# esc.net
KiCad netlist of a schematic drawn in EAGLE
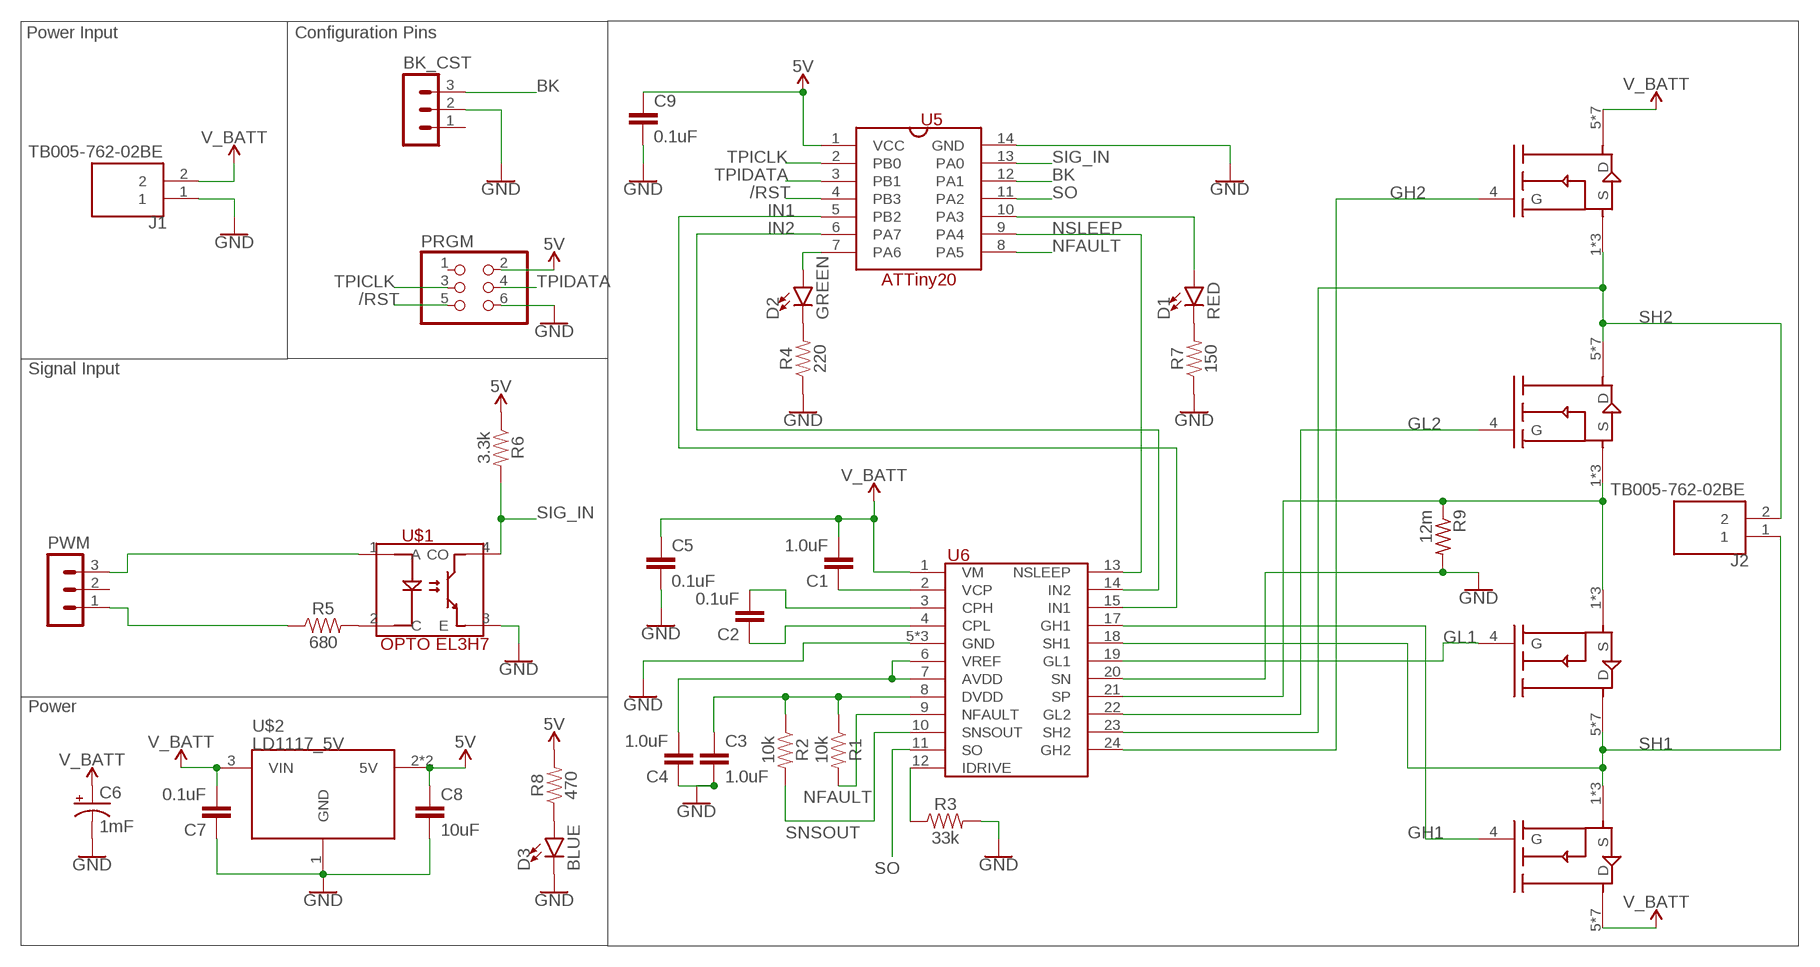
[diagram p0: schematic, sheet 1]

(export (version "E")
  (design (tool "Eeschema 10.0.6"))
  (components
    (comp (ref "BK_CST")
      (value "MA03-1")
      (footprint "eagle-import:MA03-1")
      (libsource (lib "eagle-import") (part "MA03-1"))
    )
    (comp (ref "C1")
      (value "1.0uF")
      (footprint "eagle-import:0603")
      (libsource (lib "eagle-import") (part "1.0UF-0603-16V-10%"))
    )
    (comp (ref "C2")
      (value "0.1uF")
      (footprint "eagle-import:0603")
      (libsource (lib "eagle-import") (part "0.1UF-0603-25V-5%"))
    )
    (comp (ref "C3")
      (value "1.0uF")
      (footprint "eagle-import:0603")
      (libsource (lib "eagle-import") (part "1.0UF-0603-16V-10%"))
    )
    (comp (ref "C4")
      (value "1.0uF")
      (footprint "eagle-import:0603")
      (libsource (lib "eagle-import") (part "1.0UF-0603-16V-10%"))
    )
    (comp (ref "C5")
      (value "0.1uF")
      (footprint "eagle-import:0603")
      (libsource (lib "eagle-import") (part "0.1UF-0603-25V-5%"))
    )
    (comp (ref "C6")
      (value "1mF")
      (footprint "eagle-import:CPOL-RADIAL-5MM-10MM")
      (libsource (lib "eagle-import") (part "1000UF-RADIAL-5MM-25V-20%"))
    )
    (comp (ref "C7")
      (value "0.1uF")
      (footprint "eagle-import:0603")
      (libsource (lib "eagle-import") (part "0.1UF-0603-25V-5%"))
    )
    (comp (ref "C8")
      (value "10uF")
      (footprint "eagle-import:0603")
      (libsource (lib "eagle-import") (part "10UF-0603-6.3V-20%"))
    )
    (comp (ref "C9")
      (value "0.1uF")
      (footprint "eagle-import:0603")
      (libsource (lib "eagle-import") (part "0.1UF-0603-25V-5%"))
    )
    (comp (ref "D1")
      (value "RED")
      (footprint "eagle-import:LED-0603")
      (libsource (lib "eagle-import") (part "LED-RED0603"))
    )
    (comp (ref "D2")
      (value "GREEN")
      (footprint "eagle-import:LED-0603")
      (libsource (lib "eagle-import") (part "LED-GREEN0603"))
    )
    (comp (ref "D3")
      (value "BLUE")
      (footprint "eagle-import:LED-0603")
      (libsource (lib "eagle-import") (part "LED-BLUE0603"))
    )
    (comp (ref "J1")
      (value "TB005-762-02BE")
      (footprint "eagle-import:CUI_TB005-762-02BE")
      (fields (field (name "MANUFACTURER") "CUI"))
      (libsource (lib "eagle-import") (part "TB005-762-02BE"))
    )
    (comp (ref "J2")
      (value "TB005-762-02BE")
      (footprint "eagle-import:CUI_TB005-762-02BE")
      (fields (field (name "MANUFACTURER") "CUI"))
      (libsource (lib "eagle-import") (part "TB005-762-02BE"))
    )
    (comp (ref "PRGM")
      (value "PINHD-2X3")
      (footprint "eagle-import:2X03")
      (libsource (lib "eagle-import") (part "PINHD-2X3"))
    )
    (comp (ref "PWM")
      (value "MA03-1")
      (footprint "eagle-import:MA03-1")
      (libsource (lib "eagle-import") (part "MA03-1"))
    )
    (comp (ref "R1")
      (value "10k")
      (footprint "eagle-import:0603")
      (libsource (lib "eagle-import") (part "10KOHM-0603-1/10W-1%"))
    )
    (comp (ref "R2")
      (value "10k")
      (footprint "eagle-import:0603")
      (libsource (lib "eagle-import") (part "10KOHM-0603-1/10W-1%"))
    )
    (comp (ref "R3")
      (value "33k")
      (footprint "eagle-import:0603")
      (libsource (lib "eagle-import") (part "33KOHM-0603-1/10W-1%"))
    )
    (comp (ref "R4")
      (value "220")
      (footprint "eagle-import:0603")
      (libsource (lib "eagle-import") (part "220OHM-0603-1/10W-1%"))
    )
    (comp (ref "R5")
      (value "680")
      (footprint "eagle-import:0603")
      (libsource (lib "eagle-import") (part "680OHM-0603-1/10W-5%"))
    )
    (comp (ref "R6")
      (value "3.3k")
      (footprint "eagle-import:0603")
      (libsource (lib "eagle-import") (part "3.3KOHM-0603-1/10W-1%"))
    )
    (comp (ref "R7")
      (value "150")
      (footprint "eagle-import:0603")
      (libsource (lib "eagle-import") (part "150OHM-0603-1/10W-1%"))
    )
    (comp (ref "R8")
      (value "470")
      (footprint "eagle-import:0603")
      (libsource (lib "eagle-import") (part "470OHM-0603-1/10W-1%"))
    )
    (comp (ref "R9")
      (value "12m")
      (footprint "eagle-import:R2512")
      (libsource (lib "eagle-import") (part "R-US_R2512"))
    )
    (comp (ref "U$1")
      (value "EL3H7")
      (footprint "eagle-import:SOIC127P700X265-4")
      (libsource (lib "eagle-import") (part "EL3H7"))
    )
    (comp (ref "U$2")
      (value "LD1117_5V")
      (footprint "eagle-import:SOT223")
      (libsource (lib "eagle-import") (part "LD1117_5V"))
    )
    (comp (ref "U1")
      (value "AON6558")
      (footprint "eagle-import:POWER-SO8")
      (libsource (lib "eagle-import") (part "AON6558"))
    )
    (comp (ref "U2")
      (value "AON6558")
      (footprint "eagle-import:POWER-SO8")
      (libsource (lib "eagle-import") (part "AON6558"))
    )
    (comp (ref "U3")
      (value "AON6558")
      (footprint "eagle-import:POWER-SO8")
      (libsource (lib "eagle-import") (part "AON6558"))
    )
    (comp (ref "U4")
      (value "AON6558")
      (footprint "eagle-import:POWER-SO8")
      (libsource (lib "eagle-import") (part "AON6558"))
    )
    (comp (ref "U5")
      (value "ATTINY20")
      (footprint "eagle-import:SOIC127P599X265-14")
      (libsource (lib "eagle-import") (part "ATTINY20"))
    )
    (comp (ref "U6")
      (value "DRV8701")
      (footprint "eagle-import:QFN50P400X400X100-25T280")
      (libsource (lib "eagle-import") (part "DRV8701"))
    )
  )
  (nets
    (net (code "1") (name "/BK") (class "Default")
      (node (ref "BK_CST") (pin "3") (pinfunction "3_3") (pintype "passive"))
      (node (ref "U5") (pin "12") (pinfunction "PA1_12") (pintype "bidirectional"))
    )
    (net (code "2") (name "/GH1") (class "Default")
      (node (ref "U4") (pin "4") (pinfunction "G_4") (pintype "bidirectional"))
      (node (ref "U6") (pin "17") (pinfunction "GH1_17") (pintype "bidirectional"))
    )
    (net (code "3") (name "/GH2") (class "Default")
      (node (ref "U1") (pin "4") (pinfunction "G_4") (pintype "bidirectional"))
      (node (ref "U6") (pin "24") (pinfunction "GH2_24") (pintype "bidirectional"))
    )
    (net (code "4") (name "/GL1") (class "Default")
      (node (ref "U3") (pin "4") (pinfunction "G_4") (pintype "bidirectional"))
      (node (ref "U6") (pin "19") (pinfunction "GL1_19") (pintype "bidirectional"))
    )
    (net (code "5") (name "/GL2") (class "Default")
      (node (ref "U2") (pin "4") (pinfunction "G_4") (pintype "bidirectional"))
      (node (ref "U6") (pin "22") (pinfunction "GL2_22") (pintype "bidirectional"))
    )
    (net (code "6") (name "/IN1") (class "Default")
      (node (ref "U5") (pin "5") (pinfunction "PB2_5") (pintype "bidirectional"))
      (node (ref "U6") (pin "15") (pinfunction "IN1_15") (pintype "bidirectional"))
    )
    (net (code "7") (name "/IN2") (class "Default")
      (node (ref "U5") (pin "6") (pinfunction "PA7_6") (pintype "bidirectional"))
      (node (ref "U6") (pin "14") (pinfunction "IN2_14") (pintype "bidirectional"))
    )
    (net (code "8") (name "/NFAULT") (class "Default")
      (node (ref "R1") (pin "2") (pinfunction "2_2") (pintype "passive"))
      (node (ref "U5") (pin "8") (pinfunction "PA5_8") (pintype "bidirectional"))
      (node (ref "U6") (pin "9") (pinfunction "NFAULT_9") (pintype "bidirectional"))
    )
    (net (code "9") (name "/NSLEEP") (class "Default")
      (node (ref "U5") (pin "9") (pinfunction "PA4_9") (pintype "bidirectional"))
      (node (ref "U6") (pin "13") (pinfunction "NSLEEP_13") (pintype "bidirectional"))
    )
    (net (code "10") (name "/SH1") (class "Default")
      (node (ref "J2") (pin "1") (pinfunction "1_1") (pintype "passive"))
      (node (ref "U3") (pin "5") (pinfunction "D_5") (pintype "bidirectional"))
      (node (ref "U3") (pin "6") (pinfunction "D_6") (pintype "bidirectional"))
      (node (ref "U3") (pin "7") (pinfunction "D_7") (pintype "bidirectional"))
      (node (ref "U3") (pin "8") (pinfunction "D_8") (pintype "bidirectional"))
      (node (ref "U3") (pin "PAD") (pinfunction "D_PAD") (pintype "bidirectional"))
      (node (ref "U3") (pin "SIDEPAD1") (pinfunction "D_SIDEPAD1") (pintype "bidirectional"))
      (node (ref "U3") (pin "SIDEPAD2") (pinfunction "D_SIDEPAD2") (pintype "bidirectional"))
      (node (ref "U4") (pin "1") (pinfunction "S_1") (pintype "bidirectional"))
      (node (ref "U4") (pin "2") (pinfunction "S_2") (pintype "bidirectional"))
      (node (ref "U4") (pin "3") (pinfunction "S_3") (pintype "bidirectional"))
      (node (ref "U6") (pin "18") (pinfunction "SH1_18") (pintype "bidirectional"))
    )
    (net (code "11") (name "/SH2") (class "Default")
      (node (ref "J2") (pin "2") (pinfunction "2_2") (pintype "passive"))
      (node (ref "U1") (pin "1") (pinfunction "S_1") (pintype "bidirectional"))
      (node (ref "U1") (pin "2") (pinfunction "S_2") (pintype "bidirectional"))
      (node (ref "U1") (pin "3") (pinfunction "S_3") (pintype "bidirectional"))
      (node (ref "U2") (pin "5") (pinfunction "D_5") (pintype "bidirectional"))
      (node (ref "U2") (pin "6") (pinfunction "D_6") (pintype "bidirectional"))
      (node (ref "U2") (pin "7") (pinfunction "D_7") (pintype "bidirectional"))
      (node (ref "U2") (pin "8") (pinfunction "D_8") (pintype "bidirectional"))
      (node (ref "U2") (pin "PAD") (pinfunction "D_PAD") (pintype "bidirectional"))
      (node (ref "U2") (pin "SIDEPAD1") (pinfunction "D_SIDEPAD1") (pintype "bidirectional"))
      (node (ref "U2") (pin "SIDEPAD2") (pinfunction "D_SIDEPAD2") (pintype "bidirectional"))
      (node (ref "U6") (pin "23") (pinfunction "SH2_23") (pintype "bidirectional"))
    )
    (net (code "12") (name "/SIG_IN") (class "Default")
      (node (ref "R6") (pin "2") (pinfunction "2_2") (pintype "passive"))
      (node (ref "U$1") (pin "4") (pinfunction "CO_4") (pintype "bidirectional"))
      (node (ref "U5") (pin "13") (pinfunction "PA0_13") (pintype "bidirectional"))
    )
    (net (code "13") (name "/SNSOUT") (class "Default")
      (node (ref "R2") (pin "2") (pinfunction "2_2") (pintype "passive"))
      (node (ref "U6") (pin "10") (pinfunction "SNSOUT_10") (pintype "bidirectional"))
    )
    (net (code "14") (name "/SO") (class "Default")
      (node (ref "U5") (pin "11") (pinfunction "PA2_11") (pintype "bidirectional"))
      (node (ref "U6") (pin "11") (pinfunction "SO_11") (pintype "bidirectional"))
    )
    (net (code "15") (name "/TPICLK") (class "Default")
      (node (ref "PRGM") (pin "3") (pinfunction "3_3") (pintype "passive"))
      (node (ref "U5") (pin "2") (pinfunction "PB0_2") (pintype "bidirectional"))
    )
    (net (code "16") (name "/TPIDATA") (class "Default")
      (node (ref "PRGM") (pin "4") (pinfunction "4_4") (pintype "passive"))
      (node (ref "U5") (pin "3") (pinfunction "PB1_3") (pintype "bidirectional"))
    )
    (net (code "17") (name "/{slash}RST") (class "Default")
      (node (ref "PRGM") (pin "5") (pinfunction "5_5") (pintype "passive"))
      (node (ref "U5") (pin "4") (pinfunction "PB3_4") (pintype "bidirectional"))
    )
    (net (code "18") (name "5V") (class "Default")
      (node (ref "C8") (pin "1") (pinfunction "1_1") (pintype "passive"))
      (node (ref "C9") (pin "1") (pinfunction "1_1") (pintype "passive"))
      (node (ref "PRGM") (pin "2") (pinfunction "2_2") (pintype "passive"))
      (node (ref "R6") (pin "1") (pinfunction "1_1") (pintype "passive"))
      (node (ref "R8") (pin "2") (pinfunction "2_2") (pintype "passive"))
      (node (ref "U$2") (pin "2") (pinfunction "5V_2") (pintype "bidirectional"))
      (node (ref "U$2") (pin "4") (pinfunction "5V_4") (pintype "bidirectional"))
      (node (ref "U5") (pin "1") (pinfunction "VCC_1") (pintype "bidirectional"))
    )
    (net (code "19") (name "GND") (class "Default")
      (node (ref "BK_CST") (pin "2") (pinfunction "2_2") (pintype "passive"))
      (node (ref "C3") (pin "2") (pinfunction "2_2") (pintype "passive"))
      (node (ref "C4") (pin "1") (pinfunction "1_1") (pintype "passive"))
      (node (ref "C5") (pin "2") (pinfunction "2_2") (pintype "passive"))
      (node (ref "C6") (pin "-") (pinfunction "-_-") (pintype "passive"))
      (node (ref "C7") (pin "1") (pinfunction "1_1") (pintype "passive"))
      (node (ref "C8") (pin "2") (pinfunction "2_2") (pintype "passive"))
      (node (ref "C9") (pin "2") (pinfunction "2_2") (pintype "passive"))
      (node (ref "D3") (pin "C") (pinfunction "C_C") (pintype "passive"))
      (node (ref "J1") (pin "1") (pinfunction "1_1") (pintype "passive"))
      (node (ref "PRGM") (pin "6") (pinfunction "6_6") (pintype "passive"))
      (node (ref "R3") (pin "2") (pinfunction "2_2") (pintype "passive"))
      (node (ref "R4") (pin "1") (pinfunction "1_1") (pintype "passive"))
      (node (ref "R7") (pin "1") (pinfunction "1_1") (pintype "passive"))
      (node (ref "R9") (pin "2") (pinfunction "2_2") (pintype "passive"))
      (node (ref "U$1") (pin "3") (pinfunction "E_3") (pintype "bidirectional"))
      (node (ref "U$2") (pin "1") (pinfunction "GND_1") (pintype "bidirectional"))
      (node (ref "U5") (pin "14") (pinfunction "GND_14") (pintype "bidirectional"))
      (node (ref "U6") (pin "16") (pinfunction "GND_16") (pintype "bidirectional"))
      (node (ref "U6") (pin "20") (pinfunction "SN_20") (pintype "bidirectional"))
      (node (ref "U6") (pin "25") (pinfunction "GND_25") (pintype "bidirectional"))
      (node (ref "U6") (pin "5") (pinfunction "GND_5") (pintype "bidirectional"))
    )
    (net (code "20") (name "Net-(D1-PadC)") (class "Default")
      (node (ref "D1") (pin "C") (pinfunction "C_C") (pintype "passive"))
      (node (ref "R7") (pin "2") (pinfunction "2_2") (pintype "passive"))
    )
    (net (code "21") (name "Net-(D2-PadC)") (class "Default")
      (node (ref "D2") (pin "C") (pinfunction "C_C") (pintype "passive"))
      (node (ref "R4") (pin "2") (pinfunction "2_2") (pintype "passive"))
    )
    (net (code "22") (name "Net-(D3-PadA)") (class "Default")
      (node (ref "D3") (pin "A") (pinfunction "A_A") (pintype "passive"))
      (node (ref "R8") (pin "1") (pinfunction "1_1") (pintype "passive"))
    )
    (net (code "23") (name "Net-(PWM-Pad1)") (class "Default")
      (node (ref "PWM") (pin "1") (pinfunction "1_1") (pintype "passive"))
      (node (ref "R5") (pin "1") (pinfunction "1_1") (pintype "passive"))
    )
    (net (code "24") (name "Net-(U$1-A)") (class "Default")
      (node (ref "PWM") (pin "3") (pinfunction "3_3") (pintype "passive"))
      (node (ref "U$1") (pin "1") (pinfunction "A_1") (pintype "bidirectional"))
    )
    (net (code "25") (name "Net-(U$1-C)") (class "Default")
      (node (ref "R5") (pin "2") (pinfunction "2_2") (pintype "passive"))
      (node (ref "U$1") (pin "2") (pinfunction "C_2") (pintype "bidirectional"))
    )
    (net (code "26") (name "Net-(U5-PA3)") (class "Default")
      (node (ref "D1") (pin "A") (pinfunction "A_A") (pintype "passive"))
      (node (ref "U5") (pin "10") (pinfunction "PA3_10") (pintype "bidirectional"))
    )
    (net (code "27") (name "Net-(U5-PA6)") (class "Default")
      (node (ref "D2") (pin "A") (pinfunction "A_A") (pintype "passive"))
      (node (ref "U5") (pin "7") (pinfunction "PA6_7") (pintype "bidirectional"))
    )
    (net (code "28") (name "Net-(U6-AVDD)") (class "Default")
      (node (ref "C4") (pin "2") (pinfunction "2_2") (pintype "passive"))
      (node (ref "U6") (pin "6") (pinfunction "VREF_6") (pintype "bidirectional"))
      (node (ref "U6") (pin "7") (pinfunction "AVDD_7") (pintype "bidirectional"))
    )
    (net (code "29") (name "Net-(U6-CPH)") (class "Default")
      (node (ref "C2") (pin "2") (pinfunction "2_2") (pintype "passive"))
      (node (ref "U6") (pin "3") (pinfunction "CPH_3") (pintype "bidirectional"))
    )
    (net (code "30") (name "Net-(U6-CPL)") (class "Default")
      (node (ref "C2") (pin "1") (pinfunction "1_1") (pintype "passive"))
      (node (ref "U6") (pin "4") (pinfunction "CPL_4") (pintype "bidirectional"))
    )
    (net (code "31") (name "Net-(U6-DVDD)") (class "Default")
      (node (ref "C3") (pin "1") (pinfunction "1_1") (pintype "passive"))
      (node (ref "R1") (pin "1") (pinfunction "1_1") (pintype "passive"))
      (node (ref "R2") (pin "1") (pinfunction "1_1") (pintype "passive"))
      (node (ref "U6") (pin "8") (pinfunction "DVDD_8") (pintype "bidirectional"))
    )
    (net (code "32") (name "Net-(U6-IDRIVE)") (class "Default")
      (node (ref "R3") (pin "1") (pinfunction "1_1") (pintype "passive"))
      (node (ref "U6") (pin "12") (pinfunction "IDRIVE_12") (pintype "bidirectional"))
    )
    (net (code "33") (name "Net-(U6-SP)") (class "Default")
      (node (ref "R9") (pin "1") (pinfunction "1_1") (pintype "passive"))
      (node (ref "U2") (pin "1") (pinfunction "S_1") (pintype "bidirectional"))
      (node (ref "U2") (pin "2") (pinfunction "S_2") (pintype "bidirectional"))
      (node (ref "U2") (pin "3") (pinfunction "S_3") (pintype "bidirectional"))
      (node (ref "U3") (pin "1") (pinfunction "S_1") (pintype "bidirectional"))
      (node (ref "U3") (pin "2") (pinfunction "S_2") (pintype "bidirectional"))
      (node (ref "U3") (pin "3") (pinfunction "S_3") (pintype "bidirectional"))
      (node (ref "U6") (pin "21") (pinfunction "SP_21") (pintype "bidirectional"))
    )
    (net (code "34") (name "Net-(U6-VCP)") (class "Default")
      (node (ref "C1") (pin "1") (pinfunction "1_1") (pintype "passive"))
      (node (ref "U6") (pin "2") (pinfunction "VCP_2") (pintype "bidirectional"))
    )
    (net (code "35") (name "V_BATT") (class "Default")
      (node (ref "C1") (pin "2") (pinfunction "2_2") (pintype "passive"))
      (node (ref "C5") (pin "1") (pinfunction "1_1") (pintype "passive"))
      (node (ref "C6") (pin "+") (pinfunction "+_+") (pintype "passive"))
      (node (ref "C7") (pin "2") (pinfunction "2_2") (pintype "passive"))
      (node (ref "J1") (pin "2") (pinfunction "2_2") (pintype "passive"))
      (node (ref "U$2") (pin "3") (pinfunction "VIN_3") (pintype "bidirectional"))
      (node (ref "U1") (pin "5") (pinfunction "D_5") (pintype "bidirectional"))
      (node (ref "U1") (pin "6") (pinfunction "D_6") (pintype "bidirectional"))
      (node (ref "U1") (pin "7") (pinfunction "D_7") (pintype "bidirectional"))
      (node (ref "U1") (pin "8") (pinfunction "D_8") (pintype "bidirectional"))
      (node (ref "U1") (pin "PAD") (pinfunction "D_PAD") (pintype "bidirectional"))
      (node (ref "U1") (pin "SIDEPAD1") (pinfunction "D_SIDEPAD1") (pintype "bidirectional"))
      (node (ref "U1") (pin "SIDEPAD2") (pinfunction "D_SIDEPAD2") (pintype "bidirectional"))
      (node (ref "U4") (pin "5") (pinfunction "D_5") (pintype "bidirectional"))
      (node (ref "U4") (pin "6") (pinfunction "D_6") (pintype "bidirectional"))
      (node (ref "U4") (pin "7") (pinfunction "D_7") (pintype "bidirectional"))
      (node (ref "U4") (pin "8") (pinfunction "D_8") (pintype "bidirectional"))
      (node (ref "U4") (pin "PAD") (pinfunction "D_PAD") (pintype "bidirectional"))
      (node (ref "U4") (pin "SIDEPAD1") (pinfunction "D_SIDEPAD1") (pintype "bidirectional"))
      (node (ref "U4") (pin "SIDEPAD2") (pinfunction "D_SIDEPAD2") (pintype "bidirectional"))
      (node (ref "U6") (pin "1") (pinfunction "VM_1") (pintype "bidirectional"))
    )
    (net (code "36") (name "unconnected-(BK_CST-Pad1)") (class "Default")
      (node (ref "BK_CST") (pin "1") (pinfunction "1_1") (pintype "passive"))
    )
    (net (code "37") (name "unconnected-(PRGM-Pad1)") (class "Default")
      (node (ref "PRGM") (pin "1") (pinfunction "1_1") (pintype "passive"))
    )
    (net (code "38") (name "unconnected-(PWM-Pad2)") (class "Default")
      (node (ref "PWM") (pin "2") (pinfunction "2_2") (pintype "passive"))
    )
  )
)
